# LOAD_SWITCHES.net
KiCad netlist of a schematic drawn in Altium Designer
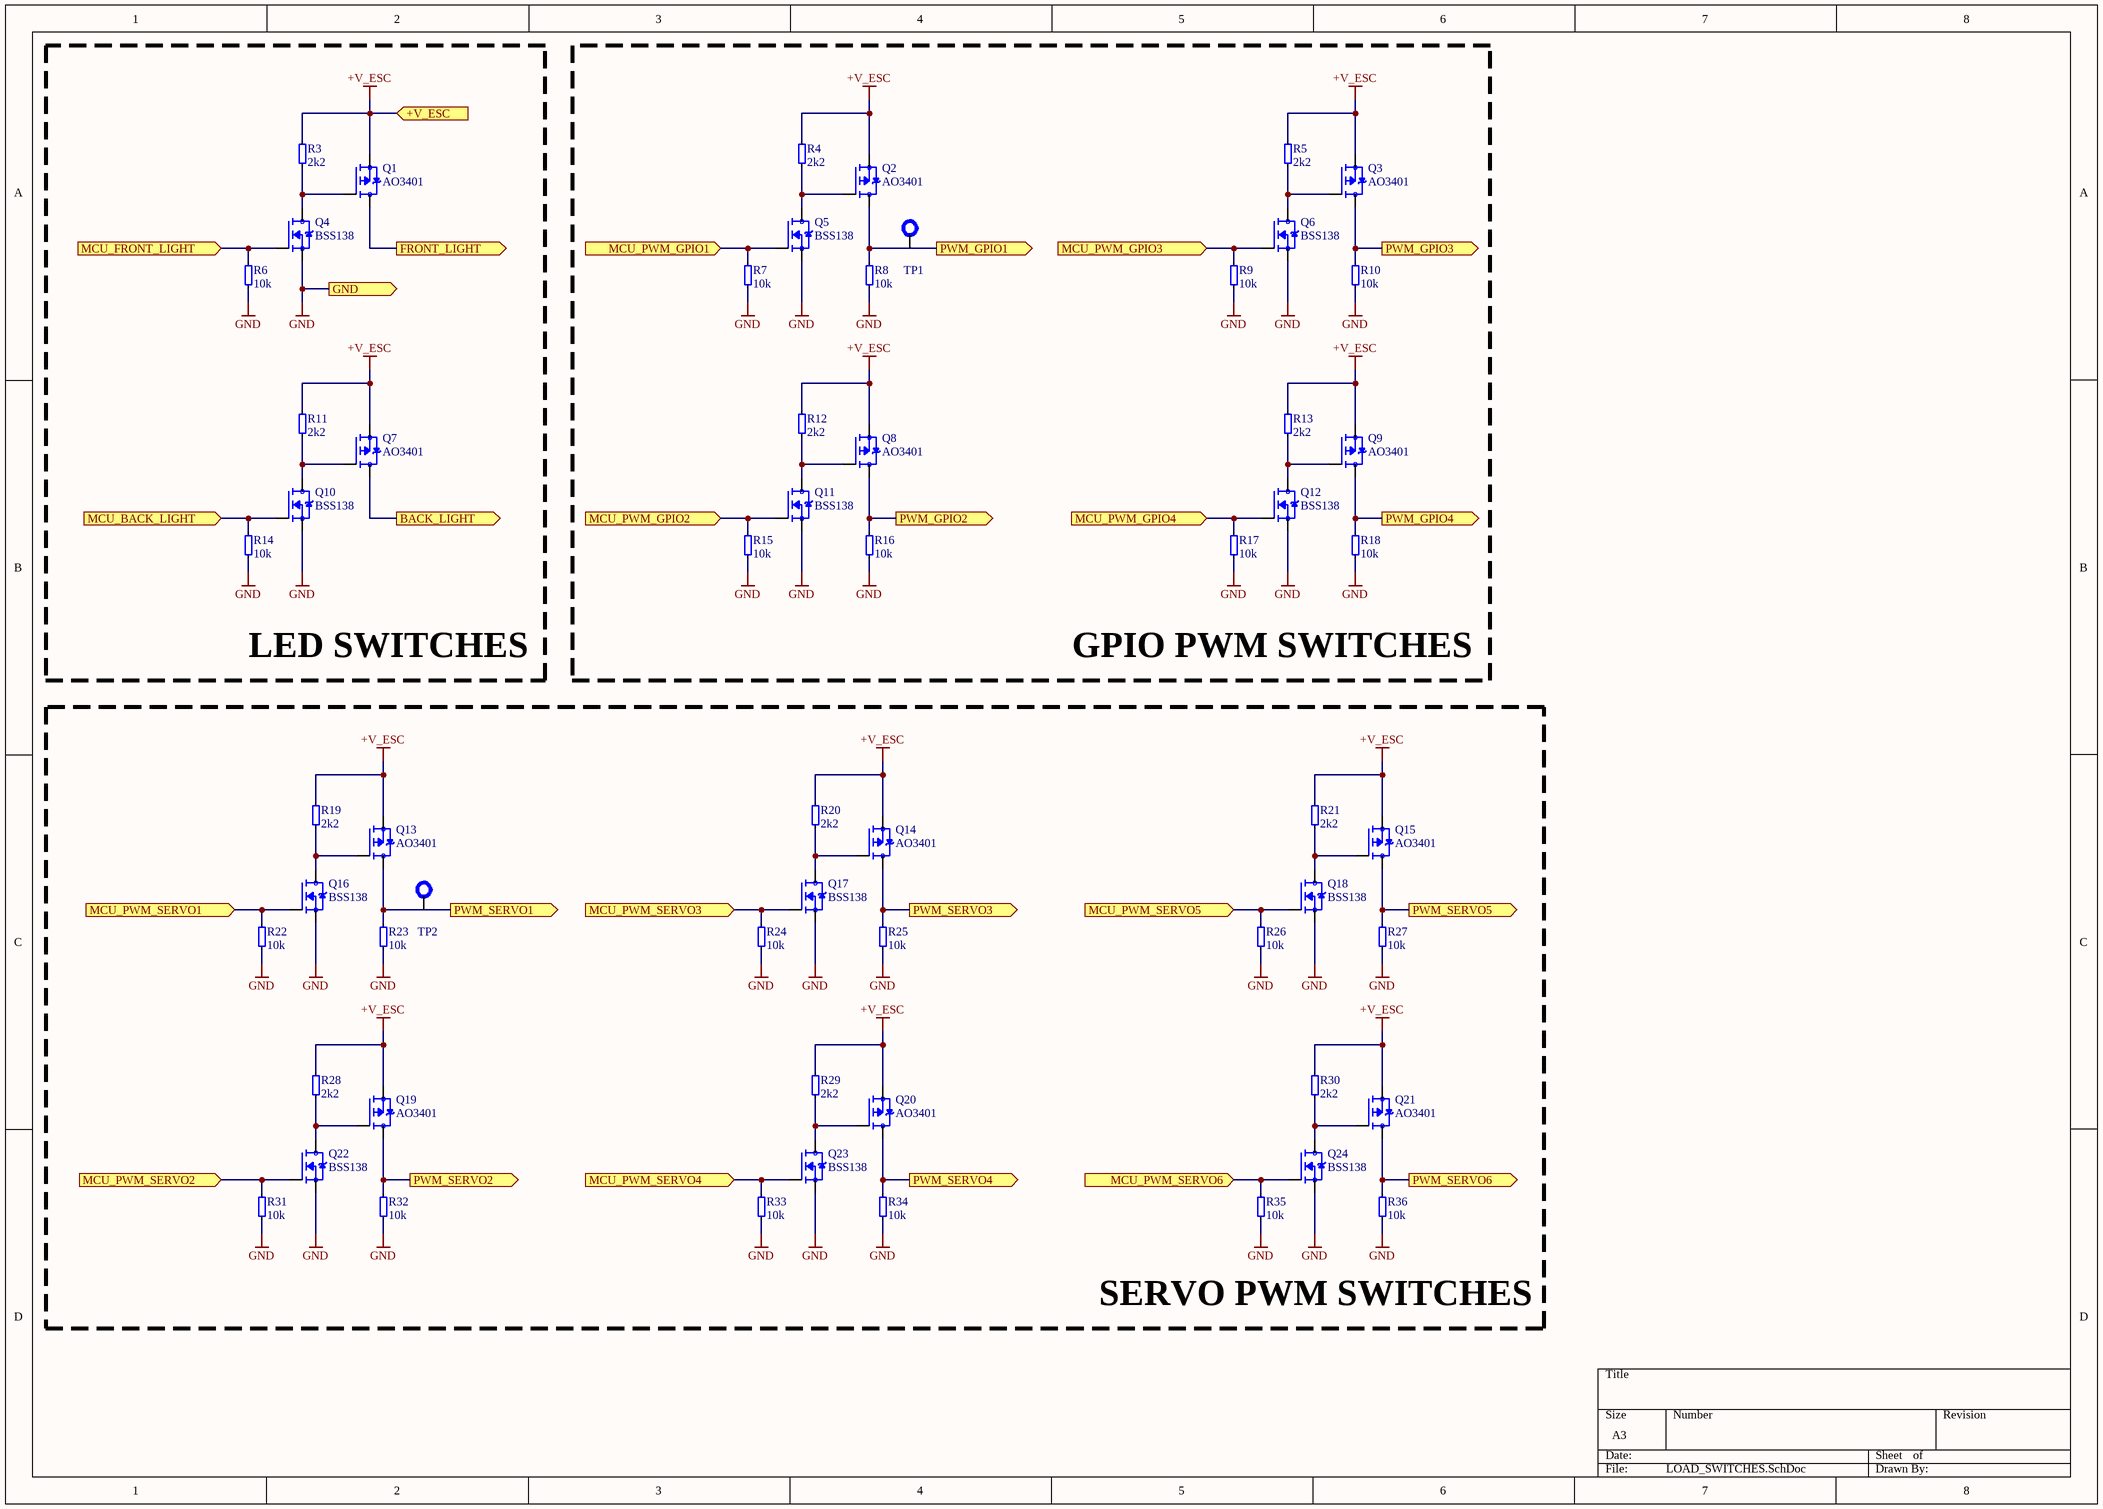
[diagram p0: LOAD_SWITCHES.SchDoc]

(export (version "E")
  (design (tool "Eeschema 10.0.6"))
  (components
    (comp (ref "Q1")
      (value "AO3401")
      (footprint "SOT95P240X111-3N")
      (description "P-Channel 30 V 4A Surface Mount SOT-23-3")
      (fields (field (name "MF") "onsemi") (field (name "MP") "BSS138"))
      (libsource (lib "Tractor2000") (part "AO3401"))
    )
    (comp (ref "Q2")
      (value "AO3401")
      (footprint "SOT95P240X111-3N")
      (description "P-Channel 30 V 4A Surface Mount SOT-23-3")
      (fields (field (name "MF") "onsemi") (field (name "MP") "BSS138"))
      (libsource (lib "Tractor2000") (part "AO3401"))
    )
    (comp (ref "Q3")
      (value "AO3401")
      (footprint "SOT95P240X111-3N")
      (description "P-Channel 30 V 4A Surface Mount SOT-23-3")
      (fields (field (name "MF") "onsemi") (field (name "MP") "BSS138"))
      (libsource (lib "Tractor2000") (part "AO3401"))
    )
    (comp (ref "Q4")
      (value "BSS138")
      (footprint "SOT95P240X111-3N")
      (description "N-Channel 50 V 220mA (Ta) 350mW (Ta) Surface Mount SOT-23-3")
      (fields (field (name "MF") "onsemi"))
      (libsource (lib "Tractor2000") (part "BSS138"))
    )
    (comp (ref "Q5")
      (value "BSS138")
      (footprint "SOT95P240X111-3N")
      (description "N-Channel 50 V 220mA (Ta) 350mW (Ta) Surface Mount SOT-23-3")
      (fields (field (name "MF") "onsemi"))
      (libsource (lib "Tractor2000") (part "BSS138"))
    )
    (comp (ref "Q6")
      (value "BSS138")
      (footprint "SOT95P240X111-3N")
      (description "N-Channel 50 V 220mA (Ta) 350mW (Ta) Surface Mount SOT-23-3")
      (fields (field (name "MF") "onsemi"))
      (libsource (lib "Tractor2000") (part "BSS138"))
    )
    (comp (ref "Q7")
      (value "AO3401")
      (footprint "SOT95P240X111-3N")
      (description "P-Channel 30 V 4A Surface Mount SOT-23-3")
      (fields (field (name "MF") "onsemi") (field (name "MP") "BSS138"))
      (libsource (lib "Tractor2000") (part "AO3401"))
    )
    (comp (ref "Q8")
      (value "AO3401")
      (footprint "SOT95P240X111-3N")
      (description "P-Channel 30 V 4A Surface Mount SOT-23-3")
      (fields (field (name "MF") "onsemi") (field (name "MP") "BSS138"))
      (libsource (lib "Tractor2000") (part "AO3401"))
    )
    (comp (ref "Q9")
      (value "AO3401")
      (footprint "SOT95P240X111-3N")
      (description "P-Channel 30 V 4A Surface Mount SOT-23-3")
      (fields (field (name "MF") "onsemi") (field (name "MP") "BSS138"))
      (libsource (lib "Tractor2000") (part "AO3401"))
    )
    (comp (ref "Q10")
      (value "BSS138")
      (footprint "SOT95P240X111-3N")
      (description "N-Channel 50 V 220mA (Ta) 350mW (Ta) Surface Mount SOT-23-3")
      (fields (field (name "MF") "onsemi"))
      (libsource (lib "Tractor2000") (part "BSS138"))
    )
    (comp (ref "Q11")
      (value "BSS138")
      (footprint "SOT95P240X111-3N")
      (description "N-Channel 50 V 220mA (Ta) 350mW (Ta) Surface Mount SOT-23-3")
      (fields (field (name "MF") "onsemi"))
      (libsource (lib "Tractor2000") (part "BSS138"))
    )
    (comp (ref "Q12")
      (value "BSS138")
      (footprint "SOT95P240X111-3N")
      (description "N-Channel 50 V 220mA (Ta) 350mW (Ta) Surface Mount SOT-23-3")
      (fields (field (name "MF") "onsemi"))
      (libsource (lib "Tractor2000") (part "BSS138"))
    )
    (comp (ref "Q13")
      (value "AO3401")
      (footprint "SOT95P240X111-3N")
      (description "P-Channel 30 V 4A Surface Mount SOT-23-3")
      (fields (field (name "MF") "onsemi") (field (name "MP") "BSS138"))
      (libsource (lib "Tractor2000") (part "AO3401"))
    )
    (comp (ref "Q14")
      (value "AO3401")
      (footprint "SOT95P240X111-3N")
      (description "P-Channel 30 V 4A Surface Mount SOT-23-3")
      (fields (field (name "MF") "onsemi") (field (name "MP") "BSS138"))
      (libsource (lib "Tractor2000") (part "AO3401"))
    )
    (comp (ref "Q15")
      (value "AO3401")
      (footprint "SOT95P240X111-3N")
      (description "P-Channel 30 V 4A Surface Mount SOT-23-3")
      (fields (field (name "MF") "onsemi") (field (name "MP") "BSS138"))
      (libsource (lib "Tractor2000") (part "AO3401"))
    )
    (comp (ref "Q16")
      (value "BSS138")
      (footprint "SOT95P240X111-3N")
      (description "N-Channel 50 V 220mA (Ta) 350mW (Ta) Surface Mount SOT-23-3")
      (fields (field (name "MF") "onsemi"))
      (libsource (lib "Tractor2000") (part "BSS138"))
    )
    (comp (ref "Q17")
      (value "BSS138")
      (footprint "SOT95P240X111-3N")
      (description "N-Channel 50 V 220mA (Ta) 350mW (Ta) Surface Mount SOT-23-3")
      (fields (field (name "MF") "onsemi"))
      (libsource (lib "Tractor2000") (part "BSS138"))
    )
    (comp (ref "Q18")
      (value "BSS138")
      (footprint "SOT95P240X111-3N")
      (description "N-Channel 50 V 220mA (Ta) 350mW (Ta) Surface Mount SOT-23-3")
      (fields (field (name "MF") "onsemi"))
      (libsource (lib "Tractor2000") (part "BSS138"))
    )
    (comp (ref "Q19")
      (value "AO3401")
      (footprint "SOT95P240X111-3N")
      (description "P-Channel 30 V 4A Surface Mount SOT-23-3")
      (fields (field (name "MF") "onsemi") (field (name "MP") "BSS138"))
      (libsource (lib "Tractor2000") (part "AO3401"))
    )
    (comp (ref "Q20")
      (value "AO3401")
      (footprint "SOT95P240X111-3N")
      (description "P-Channel 30 V 4A Surface Mount SOT-23-3")
      (fields (field (name "MF") "onsemi") (field (name "MP") "BSS138"))
      (libsource (lib "Tractor2000") (part "AO3401"))
    )
    (comp (ref "Q21")
      (value "AO3401")
      (footprint "SOT95P240X111-3N")
      (description "P-Channel 30 V 4A Surface Mount SOT-23-3")
      (fields (field (name "MF") "onsemi") (field (name "MP") "BSS138"))
      (libsource (lib "Tractor2000") (part "AO3401"))
    )
    (comp (ref "Q22")
      (value "BSS138")
      (footprint "SOT95P240X111-3N")
      (description "N-Channel 50 V 220mA (Ta) 350mW (Ta) Surface Mount SOT-23-3")
      (fields (field (name "MF") "onsemi"))
      (libsource (lib "Tractor2000") (part "BSS138"))
    )
    (comp (ref "Q23")
      (value "BSS138")
      (footprint "SOT95P240X111-3N")
      (description "N-Channel 50 V 220mA (Ta) 350mW (Ta) Surface Mount SOT-23-3")
      (fields (field (name "MF") "onsemi"))
      (libsource (lib "Tractor2000") (part "BSS138"))
    )
    (comp (ref "Q24")
      (value "BSS138")
      (footprint "SOT95P240X111-3N")
      (description "N-Channel 50 V 220mA (Ta) 350mW (Ta) Surface Mount SOT-23-3")
      (fields (field (name "MF") "onsemi"))
      (libsource (lib "Tractor2000") (part "BSS138"))
    )
    (comp (ref "R3")
      (value "2k2")
      (footprint "R0402")
      (description "Generic 0402 SMD Resistor")
      (libsource (lib "PolSl Racing - Electrical") (part "Resistor"))
    )
    (comp (ref "R4")
      (value "2k2")
      (footprint "R0402")
      (description "Generic 0402 SMD Resistor")
      (libsource (lib "PolSl Racing - Electrical") (part "Resistor"))
    )
    (comp (ref "R5")
      (value "2k2")
      (footprint "R0402")
      (description "Generic 0402 SMD Resistor")
      (libsource (lib "PolSl Racing - Electrical") (part "Resistor"))
    )
    (comp (ref "R6")
      (value "10k")
      (footprint "R0402")
      (description "Generic 0402 SMD Resistor")
      (libsource (lib "PolSl Racing - Electrical") (part "Resistor"))
    )
    (comp (ref "R7")
      (value "10k")
      (footprint "R0402")
      (description "Generic 0402 SMD Resistor")
      (libsource (lib "PolSl Racing - Electrical") (part "Resistor"))
    )
    (comp (ref "R8")
      (value "10k")
      (footprint "R0402")
      (description "Generic 0402 SMD Resistor")
      (libsource (lib "PolSl Racing - Electrical") (part "Resistor"))
    )
    (comp (ref "R9")
      (value "10k")
      (footprint "R0402")
      (description "Generic 0402 SMD Resistor")
      (libsource (lib "PolSl Racing - Electrical") (part "Resistor"))
    )
    (comp (ref "R10")
      (value "10k")
      (footprint "R0402")
      (description "Generic 0402 SMD Resistor")
      (libsource (lib "PolSl Racing - Electrical") (part "Resistor"))
    )
    (comp (ref "R11")
      (value "2k2")
      (footprint "R0402")
      (description "Generic 0402 SMD Resistor")
      (libsource (lib "PolSl Racing - Electrical") (part "Resistor"))
    )
    (comp (ref "R12")
      (value "2k2")
      (footprint "R0402")
      (description "Generic 0402 SMD Resistor")
      (libsource (lib "PolSl Racing - Electrical") (part "Resistor"))
    )
    (comp (ref "R13")
      (value "2k2")
      (footprint "R0402")
      (description "Generic 0402 SMD Resistor")
      (libsource (lib "PolSl Racing - Electrical") (part "Resistor"))
    )
    (comp (ref "R14")
      (value "10k")
      (footprint "R0402")
      (description "Generic 0402 SMD Resistor")
      (libsource (lib "PolSl Racing - Electrical") (part "Resistor"))
    )
    (comp (ref "R15")
      (value "10k")
      (footprint "R0402")
      (description "Generic 0402 SMD Resistor")
      (libsource (lib "PolSl Racing - Electrical") (part "Resistor"))
    )
    (comp (ref "R16")
      (value "10k")
      (footprint "R0402")
      (description "Generic 0402 SMD Resistor")
      (libsource (lib "PolSl Racing - Electrical") (part "Resistor"))
    )
    (comp (ref "R17")
      (value "10k")
      (footprint "R0402")
      (description "Generic 0402 SMD Resistor")
      (libsource (lib "PolSl Racing - Electrical") (part "Resistor"))
    )
    (comp (ref "R18")
      (value "10k")
      (footprint "R0402")
      (description "Generic 0402 SMD Resistor")
      (libsource (lib "PolSl Racing - Electrical") (part "Resistor"))
    )
    (comp (ref "R19")
      (value "2k2")
      (footprint "R0402")
      (description "Generic 0402 SMD Resistor")
      (libsource (lib "PolSl Racing - Electrical") (part "Resistor"))
    )
    (comp (ref "R20")
      (value "2k2")
      (footprint "R0402")
      (description "Generic 0402 SMD Resistor")
      (libsource (lib "PolSl Racing - Electrical") (part "Resistor"))
    )
    (comp (ref "R21")
      (value "2k2")
      (footprint "R0402")
      (description "Generic 0402 SMD Resistor")
      (libsource (lib "PolSl Racing - Electrical") (part "Resistor"))
    )
    (comp (ref "R22")
      (value "10k")
      (footprint "R0402")
      (description "Generic 0402 SMD Resistor")
      (libsource (lib "PolSl Racing - Electrical") (part "Resistor"))
    )
    (comp (ref "R23")
      (value "10k")
      (footprint "R0402")
      (description "Generic 0402 SMD Resistor")
      (libsource (lib "PolSl Racing - Electrical") (part "Resistor"))
    )
    (comp (ref "R24")
      (value "10k")
      (footprint "R0402")
      (description "Generic 0402 SMD Resistor")
      (libsource (lib "PolSl Racing - Electrical") (part "Resistor"))
    )
    (comp (ref "R25")
      (value "10k")
      (footprint "R0402")
      (description "Generic 0402 SMD Resistor")
      (libsource (lib "PolSl Racing - Electrical") (part "Resistor"))
    )
    (comp (ref "R26")
      (value "10k")
      (footprint "R0402")
      (description "Generic 0402 SMD Resistor")
      (libsource (lib "PolSl Racing - Electrical") (part "Resistor"))
    )
    (comp (ref "R27")
      (value "10k")
      (footprint "R0402")
      (description "Generic 0402 SMD Resistor")
      (libsource (lib "PolSl Racing - Electrical") (part "Resistor"))
    )
    (comp (ref "R28")
      (value "2k2")
      (footprint "R0402")
      (description "Generic 0402 SMD Resistor")
      (libsource (lib "PolSl Racing - Electrical") (part "Resistor"))
    )
    (comp (ref "R29")
      (value "2k2")
      (footprint "R0402")
      (description "Generic 0402 SMD Resistor")
      (libsource (lib "PolSl Racing - Electrical") (part "Resistor"))
    )
    (comp (ref "R30")
      (value "2k2")
      (footprint "R0402")
      (description "Generic 0402 SMD Resistor")
      (libsource (lib "PolSl Racing - Electrical") (part "Resistor"))
    )
    (comp (ref "R31")
      (value "10k")
      (footprint "R0402")
      (description "Generic 0402 SMD Resistor")
      (libsource (lib "PolSl Racing - Electrical") (part "Resistor"))
    )
    (comp (ref "R32")
      (value "10k")
      (footprint "R0402")
      (description "Generic 0402 SMD Resistor")
      (libsource (lib "PolSl Racing - Electrical") (part "Resistor"))
    )
    (comp (ref "R33")
      (value "10k")
      (footprint "R0402")
      (description "Generic 0402 SMD Resistor")
      (libsource (lib "PolSl Racing - Electrical") (part "Resistor"))
    )
    (comp (ref "R34")
      (value "10k")
      (footprint "R0402")
      (description "Generic 0402 SMD Resistor")
      (libsource (lib "PolSl Racing - Electrical") (part "Resistor"))
    )
    (comp (ref "R35")
      (value "10k")
      (footprint "R0402")
      (description "Generic 0402 SMD Resistor")
      (libsource (lib "PolSl Racing - Electrical") (part "Resistor"))
    )
    (comp (ref "R36")
      (value "10k")
      (footprint "R0402")
      (description "Generic 0402 SMD Resistor")
      (libsource (lib "PolSl Racing - Electrical") (part "Resistor"))
    )
    (comp (ref "TP1") (value "TP") (footprint "TP") (libsource (lib "Tractor2000") (part "TP")))
    (comp (ref "TP2") (value "TP") (footprint "TP") (libsource (lib "Tractor2000") (part "TP")))
  )
  (nets
    (net (code "1") (name "+V_ESC") (class "Default")
      (node (ref "Q1") (pin "3") (pinfunction "D_3") (pintype "passive"))
      (node (ref "Q13") (pin "3") (pinfunction "D_3") (pintype "passive"))
      (node (ref "Q14") (pin "3") (pinfunction "D_3") (pintype "passive"))
      (node (ref "Q15") (pin "3") (pinfunction "D_3") (pintype "passive"))
      (node (ref "Q19") (pin "3") (pinfunction "D_3") (pintype "passive"))
      (node (ref "Q2") (pin "3") (pinfunction "D_3") (pintype "passive"))
      (node (ref "Q20") (pin "3") (pinfunction "D_3") (pintype "passive"))
      (node (ref "Q21") (pin "3") (pinfunction "D_3") (pintype "passive"))
      (node (ref "Q3") (pin "3") (pinfunction "D_3") (pintype "passive"))
      (node (ref "Q7") (pin "3") (pinfunction "D_3") (pintype "passive"))
      (node (ref "Q8") (pin "3") (pinfunction "D_3") (pintype "passive"))
      (node (ref "Q9") (pin "3") (pinfunction "D_3") (pintype "passive"))
      (node (ref "R11") (pin "2") (pinfunction "2_2") (pintype "passive"))
      (node (ref "R12") (pin "2") (pinfunction "2_2") (pintype "passive"))
      (node (ref "R13") (pin "2") (pinfunction "2_2") (pintype "passive"))
      (node (ref "R19") (pin "2") (pinfunction "2_2") (pintype "passive"))
      (node (ref "R20") (pin "2") (pinfunction "2_2") (pintype "passive"))
      (node (ref "R21") (pin "2") (pinfunction "2_2") (pintype "passive"))
      (node (ref "R28") (pin "2") (pinfunction "2_2") (pintype "passive"))
      (node (ref "R29") (pin "2") (pinfunction "2_2") (pintype "passive"))
      (node (ref "R3") (pin "2") (pinfunction "2_2") (pintype "passive"))
      (node (ref "R30") (pin "2") (pinfunction "2_2") (pintype "passive"))
      (node (ref "R4") (pin "2") (pinfunction "2_2") (pintype "passive"))
      (node (ref "R5") (pin "2") (pinfunction "2_2") (pintype "passive"))
    )
    (net (code "2") (name "/BACK_LIGHT") (class "Default")
      (node (ref "Q7") (pin "2") (pinfunction "S_2") (pintype "passive"))
    )
    (net (code "3") (name "/FRONT_LIGHT") (class "Default")
      (node (ref "Q1") (pin "2") (pinfunction "S_2") (pintype "passive"))
    )
    (net (code "4") (name "/MCU_BACK_LIGHT") (class "Default")
      (node (ref "Q10") (pin "1") (pinfunction "G_1") (pintype "passive"))
      (node (ref "R14") (pin "2") (pinfunction "2_2") (pintype "passive"))
    )
    (net (code "5") (name "/MCU_FRONT_LIGHT") (class "Default")
      (node (ref "Q4") (pin "1") (pinfunction "G_1") (pintype "passive"))
      (node (ref "R6") (pin "2") (pinfunction "2_2") (pintype "passive"))
    )
    (net (code "6") (name "/MCU_PWM_GPIO1") (class "Default")
      (node (ref "Q5") (pin "1") (pinfunction "G_1") (pintype "passive"))
      (node (ref "R7") (pin "2") (pinfunction "2_2") (pintype "passive"))
    )
    (net (code "7") (name "/MCU_PWM_GPIO2") (class "Default")
      (node (ref "Q11") (pin "1") (pinfunction "G_1") (pintype "passive"))
      (node (ref "R15") (pin "2") (pinfunction "2_2") (pintype "passive"))
    )
    (net (code "8") (name "/MCU_PWM_GPIO3") (class "Default")
      (node (ref "Q6") (pin "1") (pinfunction "G_1") (pintype "passive"))
      (node (ref "R9") (pin "2") (pinfunction "2_2") (pintype "passive"))
    )
    (net (code "9") (name "/MCU_PWM_GPIO4") (class "Default")
      (node (ref "Q12") (pin "1") (pinfunction "G_1") (pintype "passive"))
      (node (ref "R17") (pin "2") (pinfunction "2_2") (pintype "passive"))
    )
    (net (code "10") (name "/MCU_PWM_SERVO1") (class "Default")
      (node (ref "Q16") (pin "1") (pinfunction "G_1") (pintype "passive"))
      (node (ref "R22") (pin "2") (pinfunction "2_2") (pintype "passive"))
    )
    (net (code "11") (name "/MCU_PWM_SERVO2") (class "Default")
      (node (ref "Q22") (pin "1") (pinfunction "G_1") (pintype "passive"))
      (node (ref "R31") (pin "2") (pinfunction "2_2") (pintype "passive"))
    )
    (net (code "12") (name "/MCU_PWM_SERVO3") (class "Default")
      (node (ref "Q17") (pin "1") (pinfunction "G_1") (pintype "passive"))
      (node (ref "R24") (pin "2") (pinfunction "2_2") (pintype "passive"))
    )
    (net (code "13") (name "/MCU_PWM_SERVO4") (class "Default")
      (node (ref "Q23") (pin "1") (pinfunction "G_1") (pintype "passive"))
      (node (ref "R33") (pin "2") (pinfunction "2_2") (pintype "passive"))
    )
    (net (code "14") (name "/MCU_PWM_SERVO5") (class "Default")
      (node (ref "Q18") (pin "1") (pinfunction "G_1") (pintype "passive"))
      (node (ref "R26") (pin "2") (pinfunction "2_2") (pintype "passive"))
    )
    (net (code "15") (name "/MCU_PWM_SERVO6") (class "Default")
      (node (ref "Q24") (pin "1") (pinfunction "G_1") (pintype "passive"))
      (node (ref "R35") (pin "2") (pinfunction "2_2") (pintype "passive"))
    )
    (net (code "16") (name "/PWM_GPIO1") (class "Default")
      (node (ref "Q2") (pin "2") (pinfunction "S_2") (pintype "passive"))
      (node (ref "R8") (pin "2") (pinfunction "2_2") (pintype "passive"))
    )
    (net (code "17") (name "/PWM_GPIO2") (class "Default")
      (node (ref "Q8") (pin "2") (pinfunction "S_2") (pintype "passive"))
      (node (ref "R16") (pin "2") (pinfunction "2_2") (pintype "passive"))
    )
    (net (code "18") (name "/PWM_GPIO3") (class "Default")
      (node (ref "Q3") (pin "2") (pinfunction "S_2") (pintype "passive"))
      (node (ref "R10") (pin "2") (pinfunction "2_2") (pintype "passive"))
    )
    (net (code "19") (name "/PWM_GPIO4") (class "Default")
      (node (ref "Q9") (pin "2") (pinfunction "S_2") (pintype "passive"))
      (node (ref "R18") (pin "2") (pinfunction "2_2") (pintype "passive"))
    )
    (net (code "20") (name "/PWM_SERVO1") (class "Default")
      (node (ref "Q13") (pin "2") (pinfunction "S_2") (pintype "passive"))
      (node (ref "R23") (pin "2") (pinfunction "2_2") (pintype "passive"))
    )
    (net (code "21") (name "/PWM_SERVO2") (class "Default")
      (node (ref "Q19") (pin "2") (pinfunction "S_2") (pintype "passive"))
      (node (ref "R32") (pin "2") (pinfunction "2_2") (pintype "passive"))
    )
    (net (code "22") (name "/PWM_SERVO3") (class "Default")
      (node (ref "Q14") (pin "2") (pinfunction "S_2") (pintype "passive"))
      (node (ref "R25") (pin "2") (pinfunction "2_2") (pintype "passive"))
    )
    (net (code "23") (name "/PWM_SERVO4") (class "Default")
      (node (ref "Q20") (pin "2") (pinfunction "S_2") (pintype "passive"))
      (node (ref "R34") (pin "2") (pinfunction "2_2") (pintype "passive"))
    )
    (net (code "24") (name "/PWM_SERVO5") (class "Default")
      (node (ref "Q15") (pin "2") (pinfunction "S_2") (pintype "passive"))
      (node (ref "R27") (pin "2") (pinfunction "2_2") (pintype "passive"))
    )
    (net (code "25") (name "/PWM_SERVO6") (class "Default")
      (node (ref "Q21") (pin "2") (pinfunction "S_2") (pintype "passive"))
      (node (ref "R36") (pin "2") (pinfunction "2_2") (pintype "passive"))
    )
    (net (code "26") (name "GND") (class "Default")
      (node (ref "Q10") (pin "2") (pinfunction "S_2") (pintype "passive"))
      (node (ref "Q11") (pin "2") (pinfunction "S_2") (pintype "passive"))
      (node (ref "Q12") (pin "2") (pinfunction "S_2") (pintype "passive"))
      (node (ref "Q16") (pin "2") (pinfunction "S_2") (pintype "passive"))
      (node (ref "Q17") (pin "2") (pinfunction "S_2") (pintype "passive"))
      (node (ref "Q18") (pin "2") (pinfunction "S_2") (pintype "passive"))
      (node (ref "Q22") (pin "2") (pinfunction "S_2") (pintype "passive"))
      (node (ref "Q23") (pin "2") (pinfunction "S_2") (pintype "passive"))
      (node (ref "Q24") (pin "2") (pinfunction "S_2") (pintype "passive"))
      (node (ref "Q4") (pin "2") (pinfunction "S_2") (pintype "passive"))
      (node (ref "Q5") (pin "2") (pinfunction "S_2") (pintype "passive"))
      (node (ref "Q6") (pin "2") (pinfunction "S_2") (pintype "passive"))
      (node (ref "R10") (pin "1") (pinfunction "1_1") (pintype "passive"))
      (node (ref "R14") (pin "1") (pinfunction "1_1") (pintype "passive"))
      (node (ref "R15") (pin "1") (pinfunction "1_1") (pintype "passive"))
      (node (ref "R16") (pin "1") (pinfunction "1_1") (pintype "passive"))
      (node (ref "R17") (pin "1") (pinfunction "1_1") (pintype "passive"))
      (node (ref "R18") (pin "1") (pinfunction "1_1") (pintype "passive"))
      (node (ref "R22") (pin "1") (pinfunction "1_1") (pintype "passive"))
      (node (ref "R23") (pin "1") (pinfunction "1_1") (pintype "passive"))
      (node (ref "R24") (pin "1") (pinfunction "1_1") (pintype "passive"))
      (node (ref "R25") (pin "1") (pinfunction "1_1") (pintype "passive"))
      (node (ref "R26") (pin "1") (pinfunction "1_1") (pintype "passive"))
      (node (ref "R27") (pin "1") (pinfunction "1_1") (pintype "passive"))
      (node (ref "R31") (pin "1") (pinfunction "1_1") (pintype "passive"))
      (node (ref "R32") (pin "1") (pinfunction "1_1") (pintype "passive"))
      (node (ref "R33") (pin "1") (pinfunction "1_1") (pintype "passive"))
      (node (ref "R34") (pin "1") (pinfunction "1_1") (pintype "passive"))
      (node (ref "R35") (pin "1") (pinfunction "1_1") (pintype "passive"))
      (node (ref "R36") (pin "1") (pinfunction "1_1") (pintype "passive"))
      (node (ref "R6") (pin "1") (pinfunction "1_1") (pintype "passive"))
      (node (ref "R7") (pin "1") (pinfunction "1_1") (pintype "passive"))
      (node (ref "R8") (pin "1") (pinfunction "1_1") (pintype "passive"))
      (node (ref "R9") (pin "1") (pinfunction "1_1") (pintype "passive"))
    )
    (net (code "27") (name "Net-(Q1-G)") (class "Default")
      (node (ref "Q1") (pin "1") (pinfunction "G_1") (pintype "passive"))
      (node (ref "Q4") (pin "3") (pinfunction "D_3") (pintype "passive"))
      (node (ref "R3") (pin "1") (pinfunction "1_1") (pintype "passive"))
    )
    (net (code "28") (name "Net-(Q2-G)") (class "Default")
      (node (ref "Q2") (pin "1") (pinfunction "G_1") (pintype "passive"))
      (node (ref "Q5") (pin "3") (pinfunction "D_3") (pintype "passive"))
      (node (ref "R4") (pin "1") (pinfunction "1_1") (pintype "passive"))
    )
    (net (code "29") (name "Net-(Q3-G)") (class "Default")
      (node (ref "Q3") (pin "1") (pinfunction "G_1") (pintype "passive"))
      (node (ref "Q6") (pin "3") (pinfunction "D_3") (pintype "passive"))
      (node (ref "R5") (pin "1") (pinfunction "1_1") (pintype "passive"))
    )
    (net (code "30") (name "Net-(Q10-D)") (class "Default")
      (node (ref "Q10") (pin "3") (pinfunction "D_3") (pintype "passive"))
      (node (ref "Q7") (pin "1") (pinfunction "G_1") (pintype "passive"))
      (node (ref "R11") (pin "1") (pinfunction "1_1") (pintype "passive"))
    )
    (net (code "31") (name "Net-(Q11-D)") (class "Default")
      (node (ref "Q11") (pin "3") (pinfunction "D_3") (pintype "passive"))
      (node (ref "Q8") (pin "1") (pinfunction "G_1") (pintype "passive"))
      (node (ref "R12") (pin "1") (pinfunction "1_1") (pintype "passive"))
    )
    (net (code "32") (name "Net-(Q12-D)") (class "Default")
      (node (ref "Q12") (pin "3") (pinfunction "D_3") (pintype "passive"))
      (node (ref "Q9") (pin "1") (pinfunction "G_1") (pintype "passive"))
      (node (ref "R13") (pin "1") (pinfunction "1_1") (pintype "passive"))
    )
    (net (code "33") (name "Net-(Q13-G)") (class "Default")
      (node (ref "Q13") (pin "1") (pinfunction "G_1") (pintype "passive"))
      (node (ref "Q16") (pin "3") (pinfunction "D_3") (pintype "passive"))
      (node (ref "R19") (pin "1") (pinfunction "1_1") (pintype "passive"))
    )
    (net (code "34") (name "Net-(Q14-G)") (class "Default")
      (node (ref "Q14") (pin "1") (pinfunction "G_1") (pintype "passive"))
      (node (ref "Q17") (pin "3") (pinfunction "D_3") (pintype "passive"))
      (node (ref "R20") (pin "1") (pinfunction "1_1") (pintype "passive"))
    )
    (net (code "35") (name "Net-(Q15-G)") (class "Default")
      (node (ref "Q15") (pin "1") (pinfunction "G_1") (pintype "passive"))
      (node (ref "Q18") (pin "3") (pinfunction "D_3") (pintype "passive"))
      (node (ref "R21") (pin "1") (pinfunction "1_1") (pintype "passive"))
    )
    (net (code "36") (name "Net-(Q19-G)") (class "Default")
      (node (ref "Q19") (pin "1") (pinfunction "G_1") (pintype "passive"))
      (node (ref "Q22") (pin "3") (pinfunction "D_3") (pintype "passive"))
      (node (ref "R28") (pin "1") (pinfunction "1_1") (pintype "passive"))
    )
    (net (code "37") (name "Net-(Q20-G)") (class "Default")
      (node (ref "Q20") (pin "1") (pinfunction "G_1") (pintype "passive"))
      (node (ref "Q23") (pin "3") (pinfunction "D_3") (pintype "passive"))
      (node (ref "R29") (pin "1") (pinfunction "1_1") (pintype "passive"))
    )
    (net (code "38") (name "Net-(Q21-G)") (class "Default")
      (node (ref "Q21") (pin "1") (pinfunction "G_1") (pintype "passive"))
      (node (ref "Q24") (pin "3") (pinfunction "D_3") (pintype "passive"))
      (node (ref "R30") (pin "1") (pinfunction "1_1") (pintype "passive"))
    )
    (net (code "39") (name "unconnected-(TP1-Pad1)") (class "Default")
      (node (ref "TP1") (pin "1") (pinfunction "1_1") (pintype "passive"))
    )
    (net (code "40") (name "unconnected-(TP2-Pad1)") (class "Default")
      (node (ref "TP2") (pin "1") (pinfunction "1_1") (pintype "passive"))
    )
  )
)
